# USB.net
KiCad netlist of a schematic drawn in Altium Designer
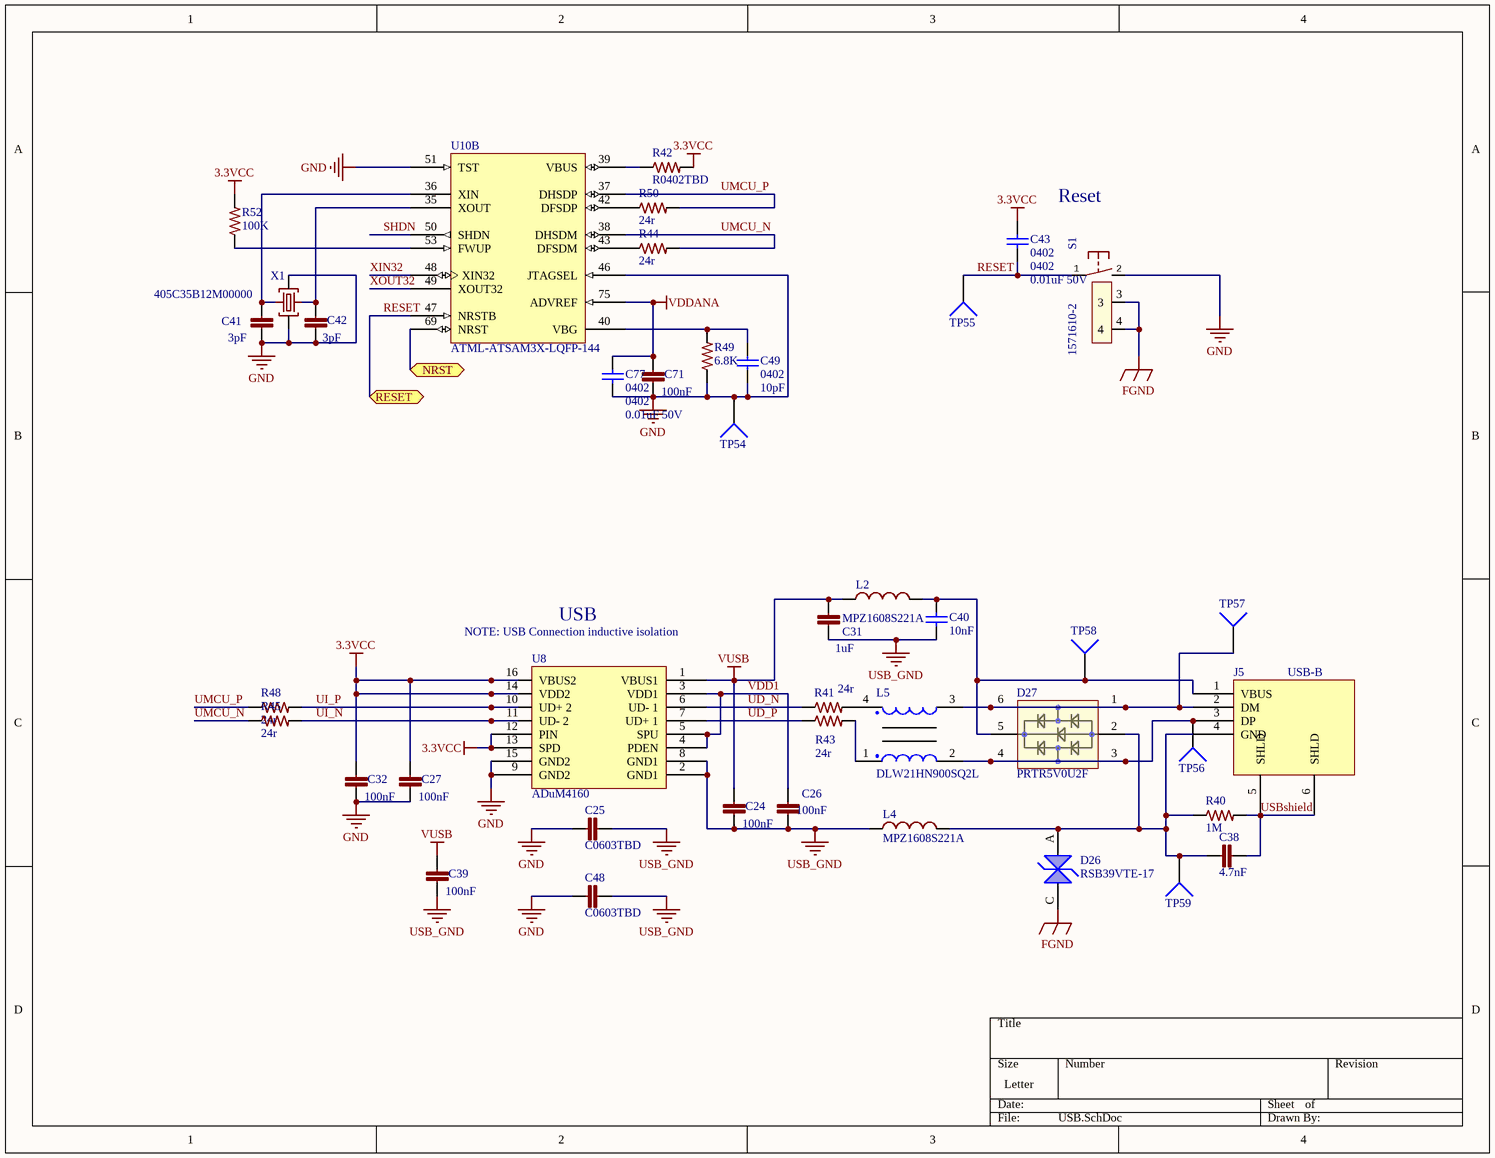
[diagram p0: USB.SchDoc]

(export (version "E")
  (design (tool "Eeschema 10.0.6"))
  (components
    (comp (ref "C24")
      (value "100nF")
      (footprint "C0402")
      (description "CAP CER 0402 100nF 16V 10% X7R")
      (fields
        (field (name "MANUFACTURERPARTNUMBER") "GRM155R71C104KA88D")
        (field (name "PUBLISHER") "UltiMachine")
      )
      (libsource (lib "3Delight") (part "GRM155R71C104KA88D"))
    )
    (comp (ref "C25")
      (value "C0603TBD")
      (footprint "C0603")
      (description "Capacitor Non Polarized")
      (fields (field (name "PUBLISHER") "UltiMachine"))
      (libsource (lib "3Delight") (part "C0603TBD"))
    )
    (comp (ref "C26")
      (value "100nF")
      (footprint "C0402")
      (description "CAP CER 0402 100nF 16V 10% X7R")
      (fields
        (field (name "MANUFACTURERPARTNUMBER") "GRM155R71C104KA88D")
        (field (name "PUBLISHER") "UltiMachine")
      )
      (libsource (lib "3Delight") (part "GRM155R71C104KA88D"))
    )
    (comp (ref "C27")
      (value "100nF")
      (footprint "C0402")
      (description "CAP CER 0402 100nF 16V 10% X7R")
      (fields
        (field (name "MANUFACTURERPARTNUMBER") "GRM155R71C104KA88D")
        (field (name "PUBLISHER") "UltiMachine")
      )
      (libsource (lib "3Delight") (part "GRM155R71C104KA88D"))
    )
    (comp (ref "C31")
      (value "1uF")
      (footprint "C0402")
      (description "CAP CER 0402 1uF 6.3V 10% X5R")
      (fields
        (field (name "MANUFACTURERPARTNUMBER") "GRM155R60J105KE19D")
        (field (name "PUBLISHER") "UltiMachine")
      )
      (libsource (lib "3Delight") (part "GRM155R60J105KE19D"))
    )
    (comp (ref "C32")
      (value "100nF")
      (footprint "C0402")
      (description "CAP CER 0402 100nF 16V 10% X7R")
      (fields
        (field (name "MANUFACTURERPARTNUMBER") "GRM155R71C104KA88D")
        (field (name "PUBLISHER") "UltiMachine")
      )
      (libsource (lib "3Delight") (part "GRM155R71C104KA88D"))
    )
    (comp (ref "C38")
      (value "4.7nF")
      (footprint "C0402")
      (description "CAP CER 0402 4.7nF 25V 10% X7R")
      (fields
        (field (name "MANUFACTURERPARTNUMBER") "CC0402KRX7R8BB472")
        (field (name "PUBLISHER") "UltiMachine")
      )
      (libsource (lib "3Delight") (part "CC0402KRX7R8BB472"))
    )
    (comp (ref "C39")
      (value "100nF")
      (footprint "C0402")
      (description "CAP CER 0402 100nF 16V 10% X7R")
      (fields
        (field (name "MANUFACTURERPARTNUMBER") "GRM155R71C104KA88D")
        (field (name "PUBLISHER") "UltiMachine")
      )
      (libsource (lib "3Delight") (part "GRM155R71C104KA88D"))
    )
    (comp (ref "C40")
      (value "10nF")
      (footprint "C0402")
      (description "CAP CER 10nF 50V X7R 0402")
      (fields
        (field (name "MFR PART #") "GRM155R71H103JA88D")
        (field (name "MFR") "Murata")
        (field (name "PUBLISHER") "Ultimachine")
      )
      (libsource (lib "Tigershark3D") (part "GRM155R71H103JA88D"))
    )
    (comp (ref "C41")
      (value "3pF")
      (footprint "C0603")
      (description "CAP CER 3PF 50V NP0 0603")
      (fields
        (field (name "MANUFACTURERPARTNUMBER") "CL10C030BB8NNND")
        (field (name "PUBLISHER") "UltiMachine")
      )
      (libsource (lib "3Delight") (part "CL10C030BB8NNND"))
    )
    (comp (ref "C42")
      (value "3pF")
      (footprint "C0603")
      (description "CAP CER 3PF 50V NP0 0603")
      (fields
        (field (name "MANUFACTURERPARTNUMBER") "CL10C030BB8NNND")
        (field (name "PUBLISHER") "UltiMachine")
      )
      (libsource (lib "3Delight") (part "CL10C030BB8NNND"))
    )
    (comp (ref "C43")
      (value "0402")
      (footprint "C0402")
      (description "CAP CER 10nF 50V X7R 0402")
      (fields
        (field (name "MFR PART #") "GRM155R71H103JA88D")
        (field (name "MFR") "Murata")
        (field (name "PACKAGEREFERENCE") "0402")
        (field (name "ALTIUM_VALUE") "0.01uF 50V")
        (field (name "PUBLISHER") "Ultimachine")
      )
      (libsource (lib "Tigershark3D") (part "GRM155R71H103JA88D"))
    )
    (comp (ref "C48")
      (value "C0603TBD")
      (footprint "C0603")
      (description "Capacitor Non Polarized")
      (fields (field (name "PUBLISHER") "UltiMachine"))
      (libsource (lib "3Delight") (part "C0603TBD"))
    )
    (comp (ref "C49")
      (value "0402")
      (footprint "C0402")
      (description "CAP CER 10PF 50V 5% NP0 0402")
      (fields
        (field (name "MFR PART #") "CL05C100JB5NNNC")
        (field (name "MFR") "Samsung")
        (field (name "ALTIUM_VALUE") "10pF")
        (field (name "PUBLISHER") "Ultimachine")
      )
      (libsource (lib "Tigershark3D") (part "CL05C100JB5NNNC"))
    )
    (comp (ref "C71")
      (value "100nF")
      (footprint "C0402")
      (description "CAP CER 0402 100nF 16V 10% X7R")
      (fields
        (field (name "MANUFACTURERPARTNUMBER") "GRM155R71C104KA88D")
        (field (name "PUBLISHER") "UltiMachine")
      )
      (libsource (lib "3Delight") (part "GRM155R71C104KA88D"))
    )
    (comp (ref "C77")
      (value "0402")
      (footprint "C0402")
      (description "CAP CER 10000PF 50V X7R 0402")
      (fields
        (field (name "MFR PART #") "GRM155R71H103JA88D")
        (field (name "MFR") "Murata")
        (field (name "PACKAGEREFERENCE") "0402")
        (field (name "ALTIUM_VALUE") "0.01uF 50V")
        (field (name "PUBLISHER") "Ultimachine")
      )
      (libsource (lib "Tigershark3D") (part "GRM155R71H103JA88D"))
    )
    (comp (ref "D26")
      (value "RSB39VTE-17")
      (footprint "SOD323-R")
      (description "DIODE TVS")
      (libsource (lib "3Delight") (part "RSB39VTE-17"))
    )
    (comp (ref "D27")
      (value "PRTR5V0U2F")
      (footprint "SOT886")
      (description "Rail-to-rail ESD protection devices")
      (libsource (lib "3Delight") (part "PRTR5V0U2F"))
    )
    (comp (ref "J5") (value "USB-B") (footprint "PN61729") (libsource (lib "3Delight") (part "USB-B")))
    (comp (ref "L2")
      (value "MPZ1608S221A")
      (footprint "C0603")
      (description "Ferrite")
      (fields (field (name "PUBLISHER") "UltiMachine"))
      (libsource (lib "3Delight") (part "MPZ1608S221A"))
    )
    (comp (ref "L4")
      (value "MPZ1608S221A")
      (footprint "C0603")
      (description "Ferrite")
      (fields (field (name "PUBLISHER") "UltiMachine"))
      (libsource (lib "3Delight") (part "MPZ1608S221A"))
    )
    (comp (ref "L5")
      (value "DLW21HN900SQ2L")
      (footprint "DLW21HN900SQ2L")
      (description "Common Mode Chokes Dual 90Ohm 100MHz 330mA 350mOhm DCR SMD")
      (libsource (lib "3Delight") (part "DLW21HN900SQ2L"))
    )
    (comp (ref "R40")
      (value "1M")
      (footprint "R0402")
      (description "RES 0402 1M 100mW 5%")
      (fields (field (name "MANUFACTURERPARTNUMBER") "ERJ2GEJ105X") (field (name "PUBLISHER") "UltiMachine"))
      (libsource (lib "3Delight") (part "ERJ2GEJ105X"))
    )
    (comp (ref "R41")
      (value "24r")
      (footprint "R0402")
      (description "Res Thick Film 0402 24 Ohm 1% 0.063W")
      (fields
        (field (name "MANUFACTURERPARTNUMBER") "CRCW0402200KFKED")
        (field (name "PUBLISHER") "UltiMachine")
      )
      (libsource (lib "3Delight") (part "CRCW040224R0FKED"))
    )
    (comp (ref "R42")
      (value "R0402TBD")
      (footprint "R0402")
      (description "Resistor")
      (fields (field (name "PUBLISHER") "UltiMachine"))
      (libsource (lib "3Delight") (part "R0402TBD"))
    )
    (comp (ref "R43")
      (value "24r")
      (footprint "R0402")
      (description "Res Thick Film 0402 24 Ohm 1% 0.063W")
      (fields
        (field (name "MANUFACTURERPARTNUMBER") "CRCW0402200KFKED")
        (field (name "PUBLISHER") "UltiMachine")
      )
      (libsource (lib "3Delight") (part "CRCW040224R0FKED"))
    )
    (comp (ref "R44")
      (value "24r")
      (footprint "R0402")
      (description "Res Thick Film 0402 24 Ohm 1% 0.063W")
      (fields
        (field (name "MANUFACTURERPARTNUMBER") "CRCW0402200KFKED")
        (field (name "PUBLISHER") "UltiMachine")
      )
      (libsource (lib "3Delight") (part "CRCW040224R0FKED"))
    )
    (comp (ref "R45")
      (value "24r")
      (footprint "R0402")
      (description "Res Thick Film 0402 24 Ohm 1% 0.063W")
      (fields
        (field (name "MANUFACTURERPARTNUMBER") "CRCW0402200KFKED")
        (field (name "PUBLISHER") "UltiMachine")
      )
      (libsource (lib "3Delight") (part "CRCW040224R0FKED"))
    )
    (comp (ref "R48")
      (value "24r")
      (footprint "R0402")
      (description "Res Thick Film 0402 24 Ohm 1% 0.063W")
      (fields
        (field (name "MANUFACTURERPARTNUMBER") "CRCW0402200KFKED")
        (field (name "PUBLISHER") "UltiMachine")
      )
      (libsource (lib "3Delight") (part "CRCW040224R0FKED"))
    )
    (comp (ref "R49")
      (value "6.8K")
      (footprint "R0402")
      (description "RES SMD 6.8K OHM 1% 1/16W 0402")
      (fields
        (field (name "MANUFACTURER") "Vishay Dale")
        (field (name "MANUFACTURERPARTNUMBER") "CRCW04026K80FKED")
        (field (name "PUBLISHER") "UltiMachine")
      )
      (libsource (lib "Tigershark3D") (part "CRCW04026K80FKED"))
    )
    (comp (ref "R50")
      (value "24r")
      (footprint "R0402")
      (description "Res Thick Film 0402 24 Ohm 1% 0.063W")
      (fields
        (field (name "MANUFACTURERPARTNUMBER") "CRCW0402200KFKED")
        (field (name "PUBLISHER") "UltiMachine")
      )
      (libsource (lib "3Delight") (part "CRCW040224R0FKED"))
    )
    (comp (ref "R52")
      (value "100K")
      (footprint "3Delight:R0402")
      (description "RES SMD 100K OHM 1% 1/16W 0402")
      (fields
        (field (name "MANUFACTURER") "Samsung")
        (field (name "MANUFACTURERPARTNUMBER") "RC1005F104CS")
        (field (name "PUBLISHER") "UltiMachine")
      )
      (libsource (lib "Tigershark3D") (part "RC1005F104CS"))
    )
    (comp (ref "S1")
      (value "1571610-2")
      (footprint "3Delight:B3F-31XX")
      (description "SWTCH Momentary Washable")
      (fields (field (name "MANUFACTURER") "TE") (field (name "PUBLISHER") "UltiMachine"))
      (libsource (lib "3Delight") (part "1571610-2"))
    )
    (comp (ref "TP54")
      (value "TP4")
      (footprint "TP-2")
      (description "Socket")
      (fields (field (name "PUBLISHER") "Altium Limited"))
      (libsource (lib "ZMBo Schematic Library") (part "Socket"))
    )
    (comp (ref "TP55")
      (value "TP4")
      (footprint "TP-2")
      (description "Socket")
      (fields (field (name "PUBLISHER") "Altium Limited"))
      (libsource (lib "ZMBo Schematic Library") (part "Socket"))
    )
    (comp (ref "TP56")
      (value "TP4")
      (footprint "TP-2")
      (description "Socket")
      (fields (field (name "PUBLISHER") "Altium Limited"))
      (libsource (lib "ZMBo Schematic Library") (part "Socket"))
    )
    (comp (ref "TP57")
      (value "TP4")
      (footprint "TP-2")
      (description "Socket")
      (fields (field (name "PUBLISHER") "Altium Limited"))
      (libsource (lib "ZMBo Schematic Library") (part "Socket"))
    )
    (comp (ref "TP58")
      (value "TP4")
      (footprint "TP-2")
      (description "Socket")
      (fields (field (name "PUBLISHER") "Altium Limited"))
      (libsource (lib "ZMBo Schematic Library") (part "Socket"))
    )
    (comp (ref "TP59")
      (value "TP4")
      (footprint "TP-2")
      (description "Socket")
      (fields (field (name "PUBLISHER") "Altium Limited"))
      (libsource (lib "ZMBo Schematic Library") (part "Socket"))
    )
    (comp (ref "U8")
      (value "ADuM4160")
      (footprint "ADuM4160")
      (description "USB Opto Isolator")
      (libsource (lib "ZMBo Schematic Library") (part "ADuM4160"))
    )
    (comp (ref "U10")
      (value "ATML-ATSAM3X-LQFP-144")
      (footprint "LQFP144_N")
      (libsource (lib "ZMBo Schematic Library") (part "ATML-ATSAM3X-LQFP-144"))
    )
    (comp (ref "X1")
      (value "405C35B12M00000")
      (footprint "CRYS320500")
      (description "Crystal 12MHz ±30ppm (Tol) ±50ppm (Stability) 13pF FUND 50Ohm")
      (fields (field (name "PUBLISHER") "UltiMachine"))
      (libsource (lib "3Delight") (part "405C35B12M00000"))
    )
  )
  (nets
    (net (code "1") (name "/NRST") (class "Default")
      (node (ref "U10") (pin "69") (pinfunction "NRST_69") (pintype "bidirectional"))
    )
    (net (code "2") (name "/RESET") (class "Default")
      (node (ref "C43") (pin "1") (pinfunction "1_1") (pintype "passive"))
      (node (ref "S1") (pin "1") (pinfunction "P_1") (pintype "passive"))
      (node (ref "TP55") (pin "1") (pinfunction "1_1") (pintype "passive"))
      (node (ref "U10") (pin "47") (pinfunction "NRSTB_47") (pintype "input"))
    )
    (net (code "3") (name "/SHDN") (class "Default")
      (node (ref "U10") (pin "50") (pinfunction "SHDN_50") (pintype "output"))
    )
    (net (code "4") (name "/UD_N") (class "Default")
      (node (ref "R41") (pin "1") (pinfunction "1_1") (pintype "passive"))
      (node (ref "U8") (pin "6") (pinfunction "UD-_1_6") (pintype "passive"))
    )
    (net (code "5") (name "/UD_P") (class "Default")
      (node (ref "R43") (pin "1") (pinfunction "1_1") (pintype "passive"))
      (node (ref "U8") (pin "7") (pinfunction "UD+_1_7") (pintype "passive"))
    )
    (net (code "6") (name "/UI_N") (class "Default")
      (node (ref "R45") (pin "2") (pinfunction "2_2") (pintype "passive"))
      (node (ref "U8") (pin "11") (pinfunction "UD-_2_11") (pintype "passive"))
    )
    (net (code "7") (name "/UI_P") (class "Default")
      (node (ref "R48") (pin "2") (pinfunction "2_2") (pintype "passive"))
      (node (ref "U8") (pin "10") (pinfunction "UD+_2_10") (pintype "passive"))
    )
    (net (code "8") (name "/UMCU_N") (class "Default")
      (node (ref "R44") (pin "2") (pinfunction "2_2") (pintype "passive"))
      (node (ref "R45") (pin "1") (pinfunction "1_1") (pintype "passive"))
      (node (ref "U10") (pin "38") (pinfunction "DHSDM_38") (pintype "bidirectional"))
    )
    (net (code "9") (name "/UMCU_P") (class "Default")
      (node (ref "R48") (pin "1") (pinfunction "1_1") (pintype "passive"))
      (node (ref "R50") (pin "2") (pinfunction "2_2") (pintype "passive"))
      (node (ref "U10") (pin "37") (pinfunction "DHSDP_37") (pintype "bidirectional"))
    )
    (net (code "10") (name "/USBshield") (class "Default")
      (node (ref "C38") (pin "1") (pinfunction "1_1") (pintype "passive"))
      (node (ref "J5") (pin "5") (pinfunction "SHLD_5") (pintype "passive"))
      (node (ref "J5") (pin "6") (pinfunction "SHLD_6") (pintype "passive"))
      (node (ref "R40") (pin "2") (pinfunction "2_2") (pintype "passive"))
    )
    (net (code "11") (name "/VDD1") (class "Default")
      (node (ref "C26") (pin "1") (pinfunction "1_1") (pintype "passive"))
      (node (ref "U8") (pin "3") (pinfunction "VDD1_3") (pintype "passive"))
      (node (ref "U8") (pin "4") (pinfunction "PDEN_4") (pintype "passive"))
      (node (ref "U8") (pin "5") (pinfunction "SPU_5") (pintype "passive"))
    )
    (net (code "12") (name "/XIN32") (class "Default")
      (node (ref "U10") (pin "48") (pinfunction "XIN32_48") (pintype "bidirectional"))
    )
    (net (code "13") (name "/XOUT32") (class "Default")
      (node (ref "U10") (pin "49") (pinfunction "XOUT32_49") (pintype "passive"))
    )
    (net (code "14") (name "3.3VCC") (class "Default")
      (node (ref "C27") (pin "1") (pinfunction "1_1") (pintype "passive"))
      (node (ref "C32") (pin "1") (pinfunction "1_1") (pintype "passive"))
      (node (ref "C43") (pin "2") (pinfunction "2_2") (pintype "passive"))
      (node (ref "R42") (pin "2") (pinfunction "2_2") (pintype "passive"))
      (node (ref "R52") (pin "2") (pinfunction "2_2") (pintype "passive"))
      (node (ref "U8") (pin "12") (pinfunction "PIN_12") (pintype "passive"))
      (node (ref "U8") (pin "13") (pinfunction "SPD_13") (pintype "passive"))
      (node (ref "U8") (pin "14") (pinfunction "VDD2_14") (pintype "passive"))
      (node (ref "U8") (pin "16") (pinfunction "VBUS2_16") (pintype "passive"))
    )
    (net (code "15") (name "FGND") (class "Default")
      (node (ref "D26") (pin "C") (pinfunction "C_C") (pintype "power_in"))
      (node (ref "S1") (pin "3") (pinfunction "3_3") (pintype "power_in"))
      (node (ref "S1") (pin "4") (pinfunction "4_4") (pintype "power_in"))
    )
    (net (code "16") (name "GND") (class "Default")
      (node (ref "C25") (pin "2") (pinfunction "2_2") (pintype "passive"))
      (node (ref "C27") (pin "2") (pinfunction "2_2") (pintype "passive"))
      (node (ref "C32") (pin "2") (pinfunction "2_2") (pintype "passive"))
      (node (ref "C41") (pin "2") (pinfunction "2_2") (pintype "passive"))
      (node (ref "C42") (pin "2") (pinfunction "2_2") (pintype "passive"))
      (node (ref "C48") (pin "2") (pinfunction "2_2") (pintype "passive"))
      (node (ref "C49") (pin "2") (pinfunction "2_2") (pintype "passive"))
      (node (ref "C71") (pin "2") (pinfunction "2_2") (pintype "passive"))
      (node (ref "C77") (pin "2") (pinfunction "2_2") (pintype "passive"))
      (node (ref "R49") (pin "1") (pinfunction "1_1") (pintype "passive"))
      (node (ref "S1") (pin "2") (pinfunction "S_2") (pintype "passive"))
      (node (ref "TP54") (pin "1") (pinfunction "1_1") (pintype "passive"))
      (node (ref "U10") (pin "46") (pinfunction "JTAGSEL_46") (pintype "input"))
      (node (ref "U10") (pin "51") (pinfunction "TST_51") (pintype "input"))
      (node (ref "U8") (pin "15") (pinfunction "GND2_15") (pintype "passive"))
      (node (ref "U8") (pin "9") (pinfunction "GND2_9") (pintype "passive"))
      (node (ref "X1") (pin "2") (pinfunction "GND_2") (pintype "passive"))
      (node (ref "X1") (pin "4") (pinfunction "GND_4") (pintype "passive"))
    )
    (net (code "17") (name "Net-(J5-DM)") (class "Default")
      (node (ref "D27") (pin "1") (pintype "power_in"))
      (node (ref "D27") (pin "6") (pintype "power_in"))
      (node (ref "J5") (pin "2") (pinfunction "DM_2") (pintype "passive"))
      (node (ref "L5") (pin "3") (pintype "power_in"))
      (node (ref "TP57") (pin "1") (pinfunction "1_1") (pintype "passive"))
    )
    (net (code "18") (name "Net-(J5-DP)") (class "Default")
      (node (ref "D27") (pin "3") (pintype "power_in"))
      (node (ref "D27") (pin "4") (pintype "power_in"))
      (node (ref "J5") (pin "3") (pinfunction "DP_3") (pintype "passive"))
      (node (ref "L5") (pin "2") (pintype "power_in"))
      (node (ref "TP56") (pin "1") (pinfunction "1_1") (pintype "passive"))
    )
    (net (code "19") (name "Net-(J5-GND)") (class "Default")
      (node (ref "C38") (pin "2") (pinfunction "2_2") (pintype "passive"))
      (node (ref "D26") (pin "A") (pinfunction "A_A") (pintype "power_in"))
      (node (ref "D27") (pin "2") (pintype "power_in"))
      (node (ref "J5") (pin "4") (pinfunction "GND_4") (pintype "passive"))
      (node (ref "L4") (pin "2") (pinfunction "2_2") (pintype "passive"))
      (node (ref "R40") (pin "1") (pinfunction "1_1") (pintype "passive"))
      (node (ref "TP59") (pin "1") (pinfunction "1_1") (pintype "passive"))
    )
    (net (code "20") (name "Net-(J5-VBUS)") (class "Default")
      (node (ref "C40") (pin "2") (pinfunction "2_2") (pintype "passive"))
      (node (ref "D27") (pin "5") (pintype "power_in"))
      (node (ref "J5") (pin "1") (pinfunction "VBUS_1") (pintype "passive"))
      (node (ref "L2") (pin "2") (pinfunction "2_2") (pintype "passive"))
      (node (ref "TP58") (pin "1") (pinfunction "1_1") (pintype "passive"))
    )
    (net (code "21") (name "Net-(L5-Pad1)") (class "Default")
      (node (ref "L5") (pin "1") (pintype "power_in"))
      (node (ref "R43") (pin "2") (pinfunction "2_2") (pintype "passive"))
    )
    (net (code "22") (name "Net-(L5-Pad4)") (class "Default")
      (node (ref "L5") (pin "4") (pintype "power_in"))
      (node (ref "R41") (pin "2") (pinfunction "2_2") (pintype "passive"))
    )
    (net (code "23") (name "Net-(U10B-DFSDM)") (class "Default")
      (node (ref "R44") (pin "1") (pinfunction "1_1") (pintype "passive"))
      (node (ref "U10") (pin "43") (pinfunction "DFSDM_43") (pintype "bidirectional"))
    )
    (net (code "24") (name "Net-(U10B-DFSDP)") (class "Default")
      (node (ref "R50") (pin "1") (pinfunction "1_1") (pintype "passive"))
      (node (ref "U10") (pin "42") (pinfunction "DFSDP_42") (pintype "bidirectional"))
    )
    (net (code "25") (name "Net-(U10B-FWUP)") (class "Default")
      (node (ref "R52") (pin "1") (pinfunction "1_1") (pintype "passive"))
      (node (ref "U10") (pin "53") (pinfunction "FWUP_53") (pintype "input"))
    )
    (net (code "26") (name "Net-(U10B-VBG)") (class "Default")
      (node (ref "C49") (pin "1") (pinfunction "1_1") (pintype "passive"))
      (node (ref "R49") (pin "2") (pinfunction "2_2") (pintype "passive"))
      (node (ref "U10") (pin "40") (pinfunction "VBG_40") (pintype "passive"))
    )
    (net (code "27") (name "Net-(U10B-VBUS)") (class "Default")
      (node (ref "R42") (pin "1") (pinfunction "1_1") (pintype "passive"))
      (node (ref "U10") (pin "39") (pinfunction "VBUS_39") (pintype "bidirectional"))
    )
    (net (code "28") (name "Net-(U10B-XIN)") (class "Default")
      (node (ref "C41") (pin "1") (pinfunction "1_1") (pintype "passive"))
      (node (ref "U10") (pin "36") (pinfunction "XIN_36") (pintype "passive"))
      (node (ref "X1") (pin "1") (pinfunction "C1_1") (pintype "passive"))
    )
    (net (code "29") (name "Net-(U10B-XOUT)") (class "Default")
      (node (ref "C42") (pin "1") (pinfunction "1_1") (pintype "passive"))
      (node (ref "U10") (pin "35") (pinfunction "XOUT_35") (pintype "passive"))
      (node (ref "X1") (pin "3") (pinfunction "C2_3") (pintype "passive"))
    )
    (net (code "30") (name "USB_GND") (class "Default")
      (node (ref "C24") (pin "2") (pinfunction "2_2") (pintype "passive"))
      (node (ref "C25") (pin "1") (pinfunction "1_1") (pintype "passive"))
      (node (ref "C26") (pin "2") (pinfunction "2_2") (pintype "passive"))
      (node (ref "C31") (pin "2") (pinfunction "2_2") (pintype "passive"))
      (node (ref "C39") (pin "2") (pinfunction "2_2") (pintype "passive"))
      (node (ref "C40") (pin "1") (pinfunction "1_1") (pintype "passive"))
      (node (ref "C48") (pin "1") (pinfunction "1_1") (pintype "passive"))
      (node (ref "L4") (pin "1") (pinfunction "1_1") (pintype "passive"))
      (node (ref "U8") (pin "2") (pinfunction "GND1_2") (pintype "passive"))
      (node (ref "U8") (pin "8") (pinfunction "GND1_8") (pintype "passive"))
    )
    (net (code "31") (name "VDDANA") (class "Default")
      (node (ref "C71") (pin "1") (pinfunction "1_1") (pintype "passive"))
      (node (ref "C77") (pin "1") (pinfunction "1_1") (pintype "passive"))
      (node (ref "U10") (pin "75") (pinfunction "ADVREF_75") (pintype "input"))
    )
    (net (code "32") (name "VUSB") (class "Default")
      (node (ref "C24") (pin "1") (pinfunction "1_1") (pintype "passive"))
      (node (ref "C31") (pin "1") (pinfunction "1_1") (pintype "passive"))
      (node (ref "C39") (pin "1") (pinfunction "1_1") (pintype "passive"))
      (node (ref "L2") (pin "1") (pinfunction "1_1") (pintype "passive"))
      (node (ref "U8") (pin "1") (pinfunction "VBUS1_1") (pintype "passive"))
    )
  )
)
